# Buck_converter_Page_2.net
KiCad netlist of a schematic drawn in Altium Designer
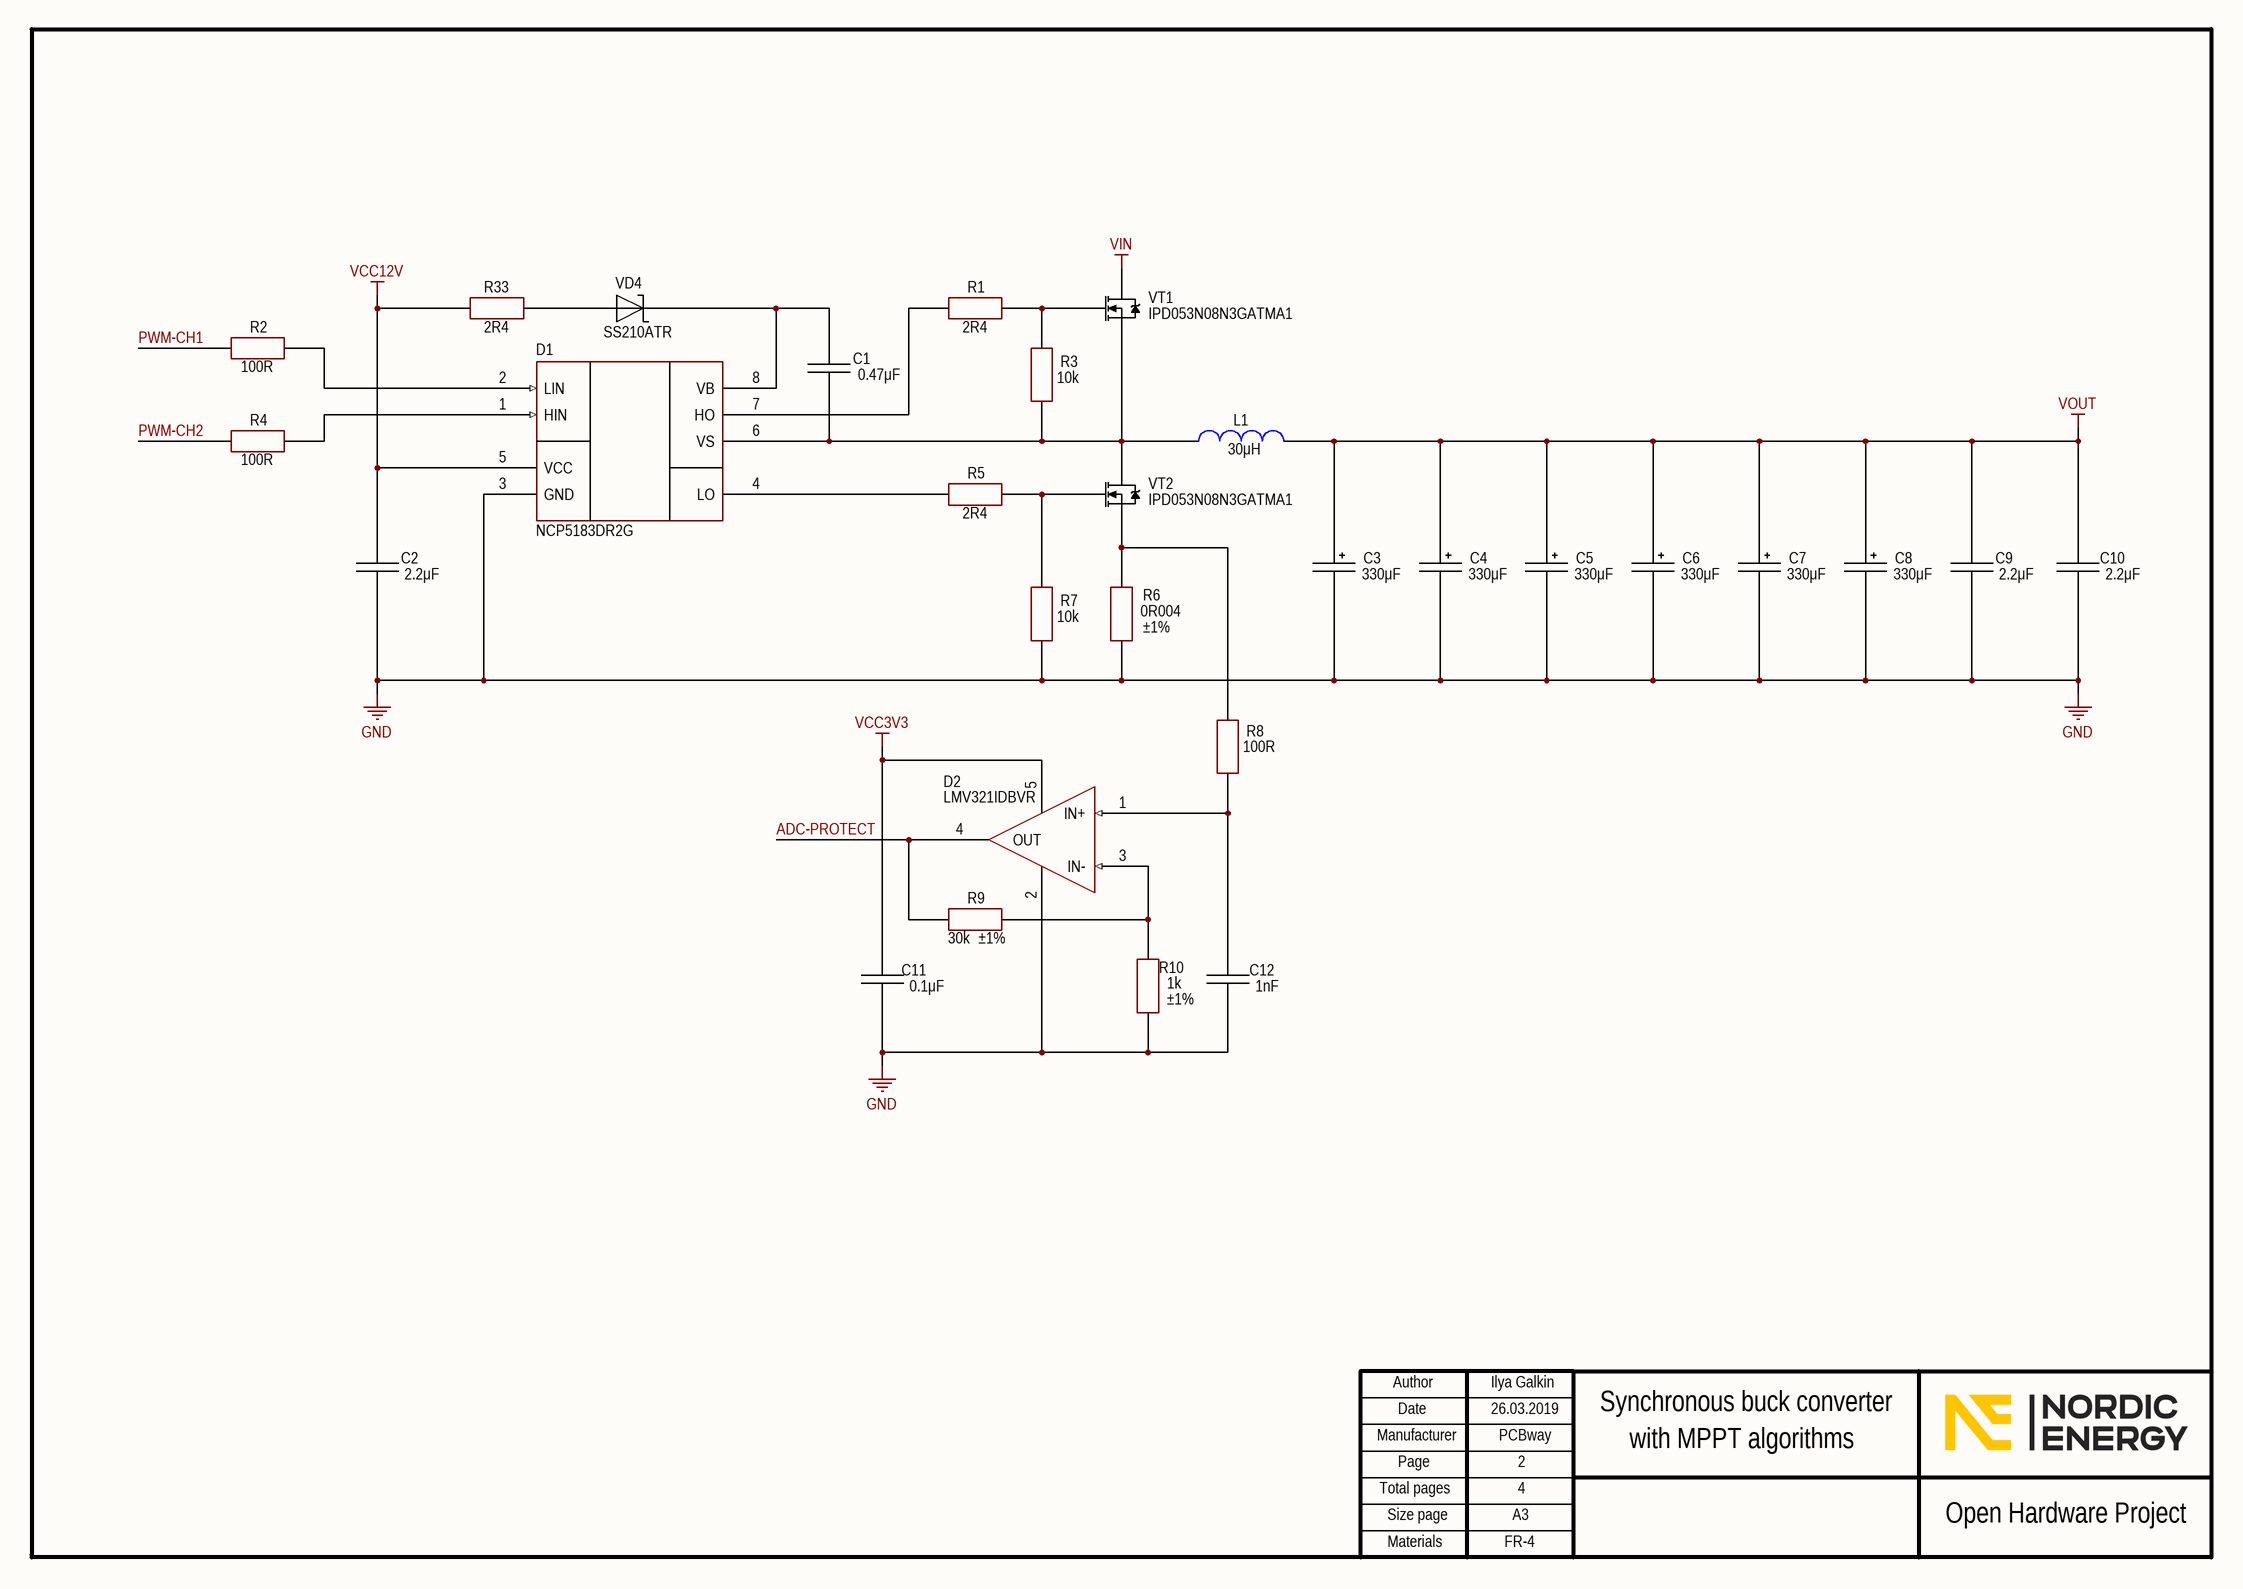
[diagram p0: Buck converter. Page 2.SchDoc]

(export (version "E")
  (design (tool "Eeschema 10.0.6"))
  (components
    (comp (ref "C1")
      (value "0.47μF")
      (footprint "CH1206C")
      (fields (field (name "MANUFACTURER") "Yageo"))
      (libsource (lib "Discrete") (part "Capacitor"))
    )
    (comp (ref "C2")
      (value "2.2μF")
      (footprint "CH1206C")
      (fields (field (name "MANUFACTURER") "Yageo"))
      (libsource (lib "Discrete") (part "Capacitor"))
    )
    (comp (ref "C3")
      (value "330μF")
      (footprint "D10C5H12.5")
      (fields (field (name "MANUFACTURER") "Panasonic"))
      (libsource (lib "Discrete") (part "AlumCap"))
    )
    (comp (ref "C4")
      (value "330μF")
      (footprint "D10C5H12.5")
      (fields (field (name "MANUFACTURER") "Panasonic"))
      (libsource (lib "Discrete") (part "AlumCap"))
    )
    (comp (ref "C5")
      (value "330μF")
      (footprint "D10C5H12.5")
      (fields (field (name "MANUFACTURER") "Panasonic"))
      (libsource (lib "Discrete") (part "AlumCap"))
    )
    (comp (ref "C6")
      (value "330μF")
      (footprint "D10C5H12.5")
      (fields (field (name "MANUFACTURER") "Panasonic"))
      (libsource (lib "Discrete") (part "AlumCap"))
    )
    (comp (ref "C7")
      (value "330μF")
      (footprint "D10C5H12.5")
      (fields (field (name "MANUFACTURER") "Panasonic"))
      (libsource (lib "Discrete") (part "AlumCap"))
    )
    (comp (ref "C8")
      (value "330μF")
      (footprint "D10C5H12.5")
      (fields (field (name "MANUFACTURER") "Panasonic"))
      (libsource (lib "Discrete") (part "AlumCap"))
    )
    (comp (ref "C9")
      (value "2.2μF")
      (footprint "CH1206C")
      (fields (field (name "MANUFACTURER") "Yageo"))
      (libsource (lib "Discrete") (part "Capacitor"))
    )
    (comp (ref "C10")
      (value "2.2μF")
      (footprint "CH1206C")
      (fields (field (name "MANUFACTURER") "Yageo"))
      (libsource (lib "Discrete") (part "Capacitor"))
    )
    (comp (ref "C11")
      (value "0.1μF")
      (footprint "CH0805C")
      (fields (field (name "MANUFACTURER") "Yageo"))
      (libsource (lib "Discrete") (part "Capacitor"))
    )
    (comp (ref "C12")
      (value "1nF")
      (footprint "CH0805C")
      (fields (field (name "MANUFACTURER") "Yageo"))
      (libsource (lib "Discrete") (part "Capacitor"))
    )
    (comp (ref "D1")
      (value "NCP5183DR2G")
      (footprint "8-SOIC")
      (description "Half-bridge")
      (fields (field (name "MANUFACTURER") "ON Semiconductor"))
      (libsource (lib "Power Supplies") (part "NCP5183DR2G"))
    )
    (comp (ref "D2")
      (value "LMV321IDBVR")
      (footprint "SOT23-5")
      (description "Amplifer")
      (fields (field (name "MANUFACTURER") "Texas Instruments"))
      (libsource (lib "Analog") (part "LMV321IDBVR"))
    )
    (comp (ref "L1")
      (value "30μH")
      (footprint "IND: R32.8/20.1/10.7 (L)")
      (fields (field (name "MANUFACTURER") "Magnetics"))
      (libsource (lib "Transformer") (part "Inductor ring"))
    )
    (comp (ref "R1")
      (value "2R4")
      (footprint "CH0805R")
      (fields (field (name "MANUFACTURER") "Yageo"))
      (libsource (lib "Discrete") (part "Resistor"))
    )
    (comp (ref "R2")
      (value "100R")
      (footprint "CH0805R")
      (fields (field (name "MANUFACTURER") "Yageo"))
      (libsource (lib "") (part "Resistor_2"))
    )
    (comp (ref "R3")
      (value "10k")
      (footprint "CH0805R")
      (fields (field (name "MANUFACTURER") "Yageo"))
      (libsource (lib "") (part "Resistor_3"))
    )
    (comp (ref "R4")
      (value "100R")
      (footprint "CH0805R")
      (fields (field (name "MANUFACTURER") "Yageo"))
      (libsource (lib "") (part "Resistor_2"))
    )
    (comp (ref "R5")
      (value "2R4")
      (footprint "CH0805R")
      (fields (field (name "MANUFACTURER") "Yageo"))
      (libsource (lib "Discrete") (part "Resistor"))
    )
    (comp (ref "R6")
      (value "0R004")
      (footprint "CH2512R")
      (fields (field (name "MANUFACTURER") "Yageo") (field (name "COMPONENTKIND") "±1%"))
      (libsource (lib "") (part "Resistor_1"))
    )
    (comp (ref "R7")
      (value "10k")
      (footprint "CH0805R")
      (fields (field (name "MANUFACTURER") "Yageo"))
      (libsource (lib "") (part "Resistor_3"))
    )
    (comp (ref "R8")
      (value "100R")
      (footprint "CH0805R")
      (fields (field (name "MANUFACTURER") "Yageo"))
      (libsource (lib "") (part "Resistor_1"))
    )
    (comp (ref "R9")
      (value "30k")
      (footprint "CH0805R")
      (fields (field (name "MANUFACTURER") "Yageo") (field (name "COMPONENTKIND") "±1%"))
      (libsource (lib "Discrete") (part "Resistor"))
    )
    (comp (ref "R10")
      (value "1k")
      (footprint "CH0805R")
      (fields (field (name "MANUFACTURER") "Yageo") (field (name "COMPONENTKIND") "±1%"))
      (libsource (lib "Discrete") (part "Resistor"))
    )
    (comp (ref "R33")
      (value "2R4")
      (footprint "CH0805R")
      (fields (field (name "MANUFACTURER") "Yageo"))
      (libsource (lib "Discrete") (part "Resistor"))
    )
    (comp (ref "VD4")
      (value "SS210ATR")
      (footprint "SMA")
      (fields (field (name "MANUFACTURER") "SMC Diode"))
      (libsource (lib "Diods") (part "Diod Schottky"))
    )
    (comp (ref "VT1")
      (value "IPD053N08N3GATMA1")
      (footprint "D2PAK")
      (description "Mosfet")
      (fields (field (name "MANUFACTURER") "Infineon"))
      (libsource (lib "Transistor") (part "N-chanel"))
    )
    (comp (ref "VT2")
      (value "IPD053N08N3GATMA1")
      (footprint "D2PAK")
      (description "Mosfet")
      (fields (field (name "MANUFACTURER") "Infineon"))
      (libsource (lib "Transistor") (part "N-chanel"))
    )
  )
  (nets
    (net (code "1") (name "/ADC-PROTECT") (class "Default")
      (node (ref "D2") (pin "4") (pinfunction "OUT_4") (pintype "power_in"))
      (node (ref "R9") (pin "2") (pinfunction "2_2") (pintype "passive"))
    )
    (net (code "2") (name "/PWM-CH1") (class "Default")
      (node (ref "R2") (pin "1") (pinfunction "1_1") (pintype "passive"))
    )
    (net (code "3") (name "/PWM-CH2") (class "Default")
      (node (ref "R4") (pin "1") (pinfunction "1_1") (pintype "passive"))
    )
    (net (code "4") (name "GND") (class "Default")
      (node (ref "C10") (pin "1") (pinfunction "1_1") (pintype "power_in"))
      (node (ref "C11") (pin "1") (pinfunction "1_1") (pintype "power_in"))
      (node (ref "C12") (pin "1") (pinfunction "1_1") (pintype "power_in"))
      (node (ref "C2") (pin "1") (pinfunction "1_1") (pintype "power_in"))
      (node (ref "C3") (pin "2") (pinfunction "2_2") (pintype "power_in"))
      (node (ref "C4") (pin "2") (pinfunction "2_2") (pintype "power_in"))
      (node (ref "C5") (pin "2") (pinfunction "2_2") (pintype "power_in"))
      (node (ref "C6") (pin "2") (pinfunction "2_2") (pintype "power_in"))
      (node (ref "C7") (pin "2") (pinfunction "2_2") (pintype "power_in"))
      (node (ref "C8") (pin "2") (pinfunction "2_2") (pintype "power_in"))
      (node (ref "C9") (pin "1") (pinfunction "1_1") (pintype "power_in"))
      (node (ref "D1") (pin "3") (pinfunction "GND_3") (pintype "passive"))
      (node (ref "D2") (pin "2") (pinfunction "V-_2") (pintype "power_in"))
      (node (ref "R10") (pin "2") (pinfunction "2_2") (pintype "passive"))
      (node (ref "R6") (pin "2") (pinfunction "2_2") (pintype "passive"))
      (node (ref "R7") (pin "1") (pinfunction "1_1") (pintype "passive"))
    )
    (net (code "5") (name "Net-(D1-HIN)") (class "Default")
      (node (ref "D1") (pin "1") (pinfunction "HIN_1") (pintype "input"))
      (node (ref "R4") (pin "2") (pinfunction "2_2") (pintype "passive"))
    )
    (net (code "6") (name "Net-(D1-HO)") (class "Default")
      (node (ref "D1") (pin "7") (pinfunction "HO_7") (pintype "passive"))
      (node (ref "R1") (pin "2") (pinfunction "2_2") (pintype "passive"))
    )
    (net (code "7") (name "Net-(D1-LIN)") (class "Default")
      (node (ref "D1") (pin "2") (pinfunction "LIN_2") (pintype "input"))
      (node (ref "R2") (pin "2") (pinfunction "2_2") (pintype "passive"))
    )
    (net (code "8") (name "Net-(D1-LO)") (class "Default")
      (node (ref "D1") (pin "4") (pinfunction "LO_4") (pintype "passive"))
      (node (ref "R5") (pin "2") (pinfunction "2_2") (pintype "passive"))
    )
    (net (code "9") (name "Net-(D1-VB)") (class "Default")
      (node (ref "C1") (pin "2") (pinfunction "2_2") (pintype "power_in"))
      (node (ref "D1") (pin "8") (pinfunction "VB_8") (pintype "passive"))
      (node (ref "VD4") (pin "2") (pinfunction "2_2") (pintype "passive"))
    )
    (net (code "10") (name "Net-(D1-VS)") (class "Default")
      (node (ref "C1") (pin "1") (pinfunction "1_1") (pintype "power_in"))
      (node (ref "D1") (pin "6") (pinfunction "VS_6") (pintype "passive"))
      (node (ref "L1") (pin "2") (pinfunction "2_2") (pintype "passive"))
      (node (ref "R3") (pin "1") (pinfunction "1_1") (pintype "passive"))
      (node (ref "VT1") (pin "3") (pinfunction "S_3") (pintype "passive"))
      (node (ref "VT2") (pin "2") (pinfunction "D_2") (pintype "passive"))
    )
    (net (code "11") (name "Net-(D2-IN+)") (class "Default")
      (node (ref "C12") (pin "2") (pinfunction "2_2") (pintype "power_in"))
      (node (ref "D2") (pin "1") (pinfunction "IN+_1") (pintype "input"))
      (node (ref "R8") (pin "2") (pinfunction "2_2") (pintype "passive"))
    )
    (net (code "12") (name "Net-(D2-IN-)") (class "Default")
      (node (ref "D2") (pin "3") (pinfunction "IN-_3") (pintype "input"))
      (node (ref "R10") (pin "1") (pinfunction "1_1") (pintype "passive"))
      (node (ref "R9") (pin "1") (pinfunction "1_1") (pintype "passive"))
    )
    (net (code "13") (name "Net-(R33-Pad1)") (class "Default")
      (node (ref "R33") (pin "1") (pinfunction "1_1") (pintype "passive"))
      (node (ref "VD4") (pin "1") (pinfunction "1_1") (pintype "passive"))
    )
    (net (code "14") (name "Net-(VT1-G)") (class "Default")
      (node (ref "R1") (pin "1") (pinfunction "1_1") (pintype "passive"))
      (node (ref "R3") (pin "2") (pinfunction "2_2") (pintype "passive"))
      (node (ref "VT1") (pin "1") (pinfunction "G_1") (pintype "passive"))
    )
    (net (code "15") (name "Net-(VT2-G)") (class "Default")
      (node (ref "R5") (pin "1") (pinfunction "1_1") (pintype "passive"))
      (node (ref "R7") (pin "2") (pinfunction "2_2") (pintype "passive"))
      (node (ref "VT2") (pin "1") (pinfunction "G_1") (pintype "passive"))
    )
    (net (code "16") (name "Net-(VT2-S)") (class "Default")
      (node (ref "R6") (pin "1") (pinfunction "1_1") (pintype "passive"))
      (node (ref "R8") (pin "1") (pinfunction "1_1") (pintype "passive"))
      (node (ref "VT2") (pin "3") (pinfunction "S_3") (pintype "passive"))
    )
    (net (code "17") (name "VCC3V3") (class "Default")
      (node (ref "C11") (pin "2") (pinfunction "2_2") (pintype "power_in"))
      (node (ref "D2") (pin "5") (pinfunction "V+_5") (pintype "power_in"))
    )
    (net (code "18") (name "VCC12V") (class "Default")
      (node (ref "C2") (pin "2") (pinfunction "2_2") (pintype "power_in"))
      (node (ref "D1") (pin "5") (pinfunction "VCC_5") (pintype "passive"))
      (node (ref "R33") (pin "2") (pinfunction "2_2") (pintype "passive"))
    )
    (net (code "19") (name "VIN") (class "Default")
      (node (ref "VT1") (pin "2") (pinfunction "D_2") (pintype "passive"))
    )
    (net (code "20") (name "VOUT") (class "Default")
      (node (ref "C10") (pin "2") (pinfunction "2_2") (pintype "power_in"))
      (node (ref "C3") (pin "1") (pinfunction "1_1") (pintype "power_in"))
      (node (ref "C4") (pin "1") (pinfunction "1_1") (pintype "power_in"))
      (node (ref "C5") (pin "1") (pinfunction "1_1") (pintype "power_in"))
      (node (ref "C6") (pin "1") (pinfunction "1_1") (pintype "power_in"))
      (node (ref "C7") (pin "1") (pinfunction "1_1") (pintype "power_in"))
      (node (ref "C8") (pin "1") (pinfunction "1_1") (pintype "power_in"))
      (node (ref "C9") (pin "2") (pinfunction "2_2") (pintype "power_in"))
      (node (ref "L1") (pin "1") (pinfunction "1_1") (pintype "passive"))
    )
  )
)
